# WMF_Ambient_SmartPot_A.net
KiCad netlist of a schematic drawn in EAGLE
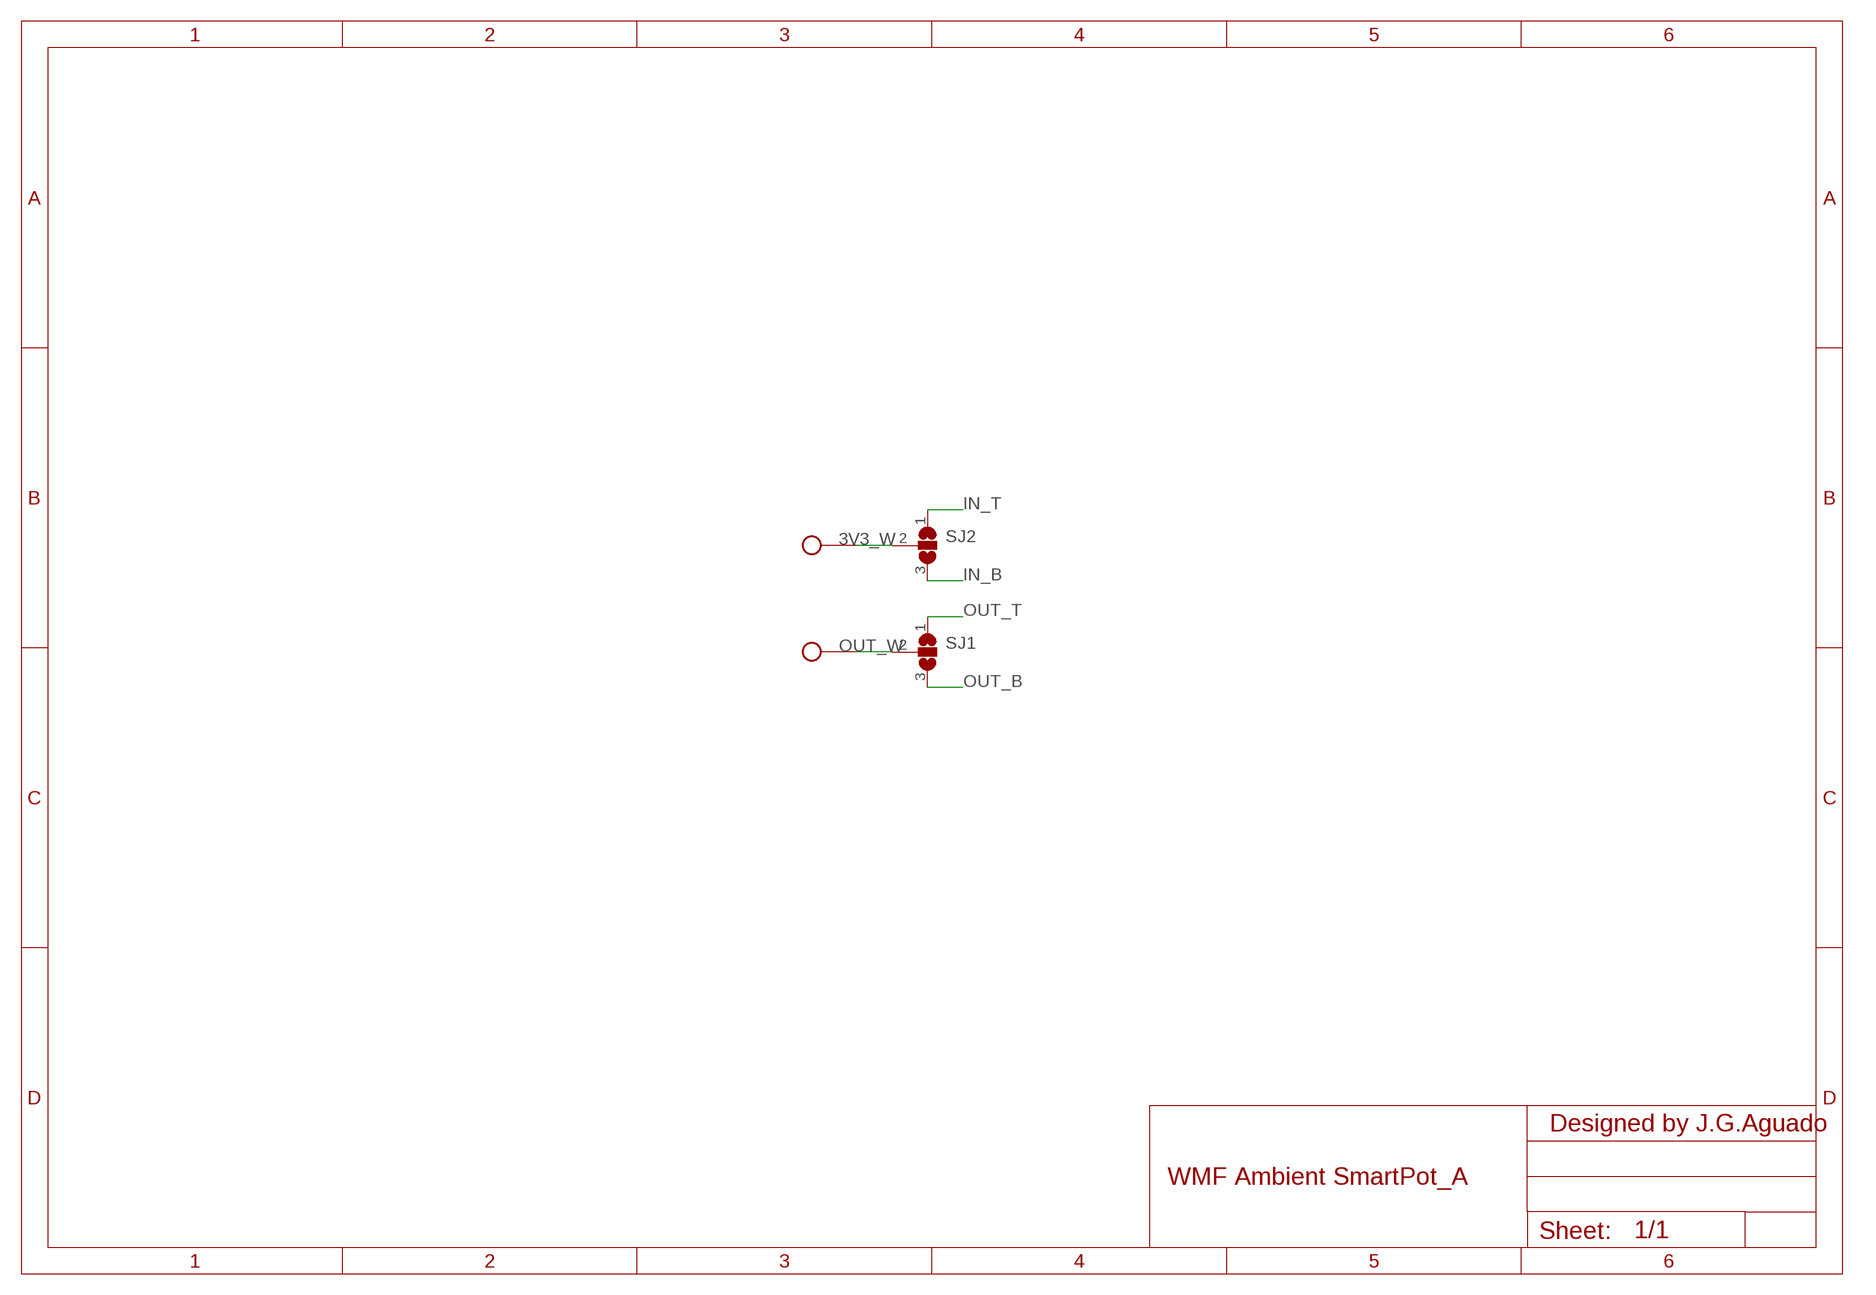
[diagram p0: schematic, sheet 1]

(export (version "E")
  (design (tool "Eeschema 10.0.6"))
  (components
    (comp (ref "SJ1")
      (value "SJ2W")
      (footprint "eagle-import:SJ_2")
      (libsource (lib "eagle-import") (part "SJ2W"))
    )
    (comp (ref "SJ2")
      (value "SJ2W")
      (footprint "eagle-import:SJ_2")
      (libsource (lib "eagle-import") (part "SJ2W"))
    )
    (comp (ref "U$4")
      (value "OVAL_3MM_HOLE")
      (footprint "eagle-import:OVAL_HOLE")
      (libsource (lib "eagle-import") (part "OVAL_3MM_HOLE"))
    )
    (comp (ref "U$5")
      (value "OVAL_3MM_HOLE")
      (footprint "eagle-import:OVAL_HOLE")
      (libsource (lib "eagle-import") (part "OVAL_3MM_HOLE"))
    )
  )
  (nets
    (net (code "1") (name "/3V3_W") (class "Default")
      (node (ref "SJ2") (pin "2") (pinfunction "2_2") (pintype "passive"))
      (node (ref "U$4") (pin "P$2") (pinfunction "P$1_P$2") (pintype "bidirectional"))
    )
    (net (code "2") (name "/IN_B") (class "Default")
      (node (ref "SJ2") (pin "3") (pinfunction "3_3") (pintype "passive"))
    )
    (net (code "3") (name "/IN_T") (class "Default")
      (node (ref "SJ2") (pin "1") (pinfunction "1_1") (pintype "passive"))
    )
    (net (code "4") (name "/OUT_B") (class "Default")
      (node (ref "SJ1") (pin "3") (pinfunction "3_3") (pintype "passive"))
    )
    (net (code "5") (name "/OUT_T") (class "Default")
      (node (ref "SJ1") (pin "1") (pinfunction "1_1") (pintype "passive"))
    )
    (net (code "6") (name "/OUT_W") (class "Default")
      (node (ref "SJ1") (pin "2") (pinfunction "2_2") (pintype "passive"))
      (node (ref "U$5") (pin "P$2") (pinfunction "P$1_P$2") (pintype "bidirectional"))
    )
  )
)
